# sch.net
KiCad netlist of a schematic drawn in EasyEDA
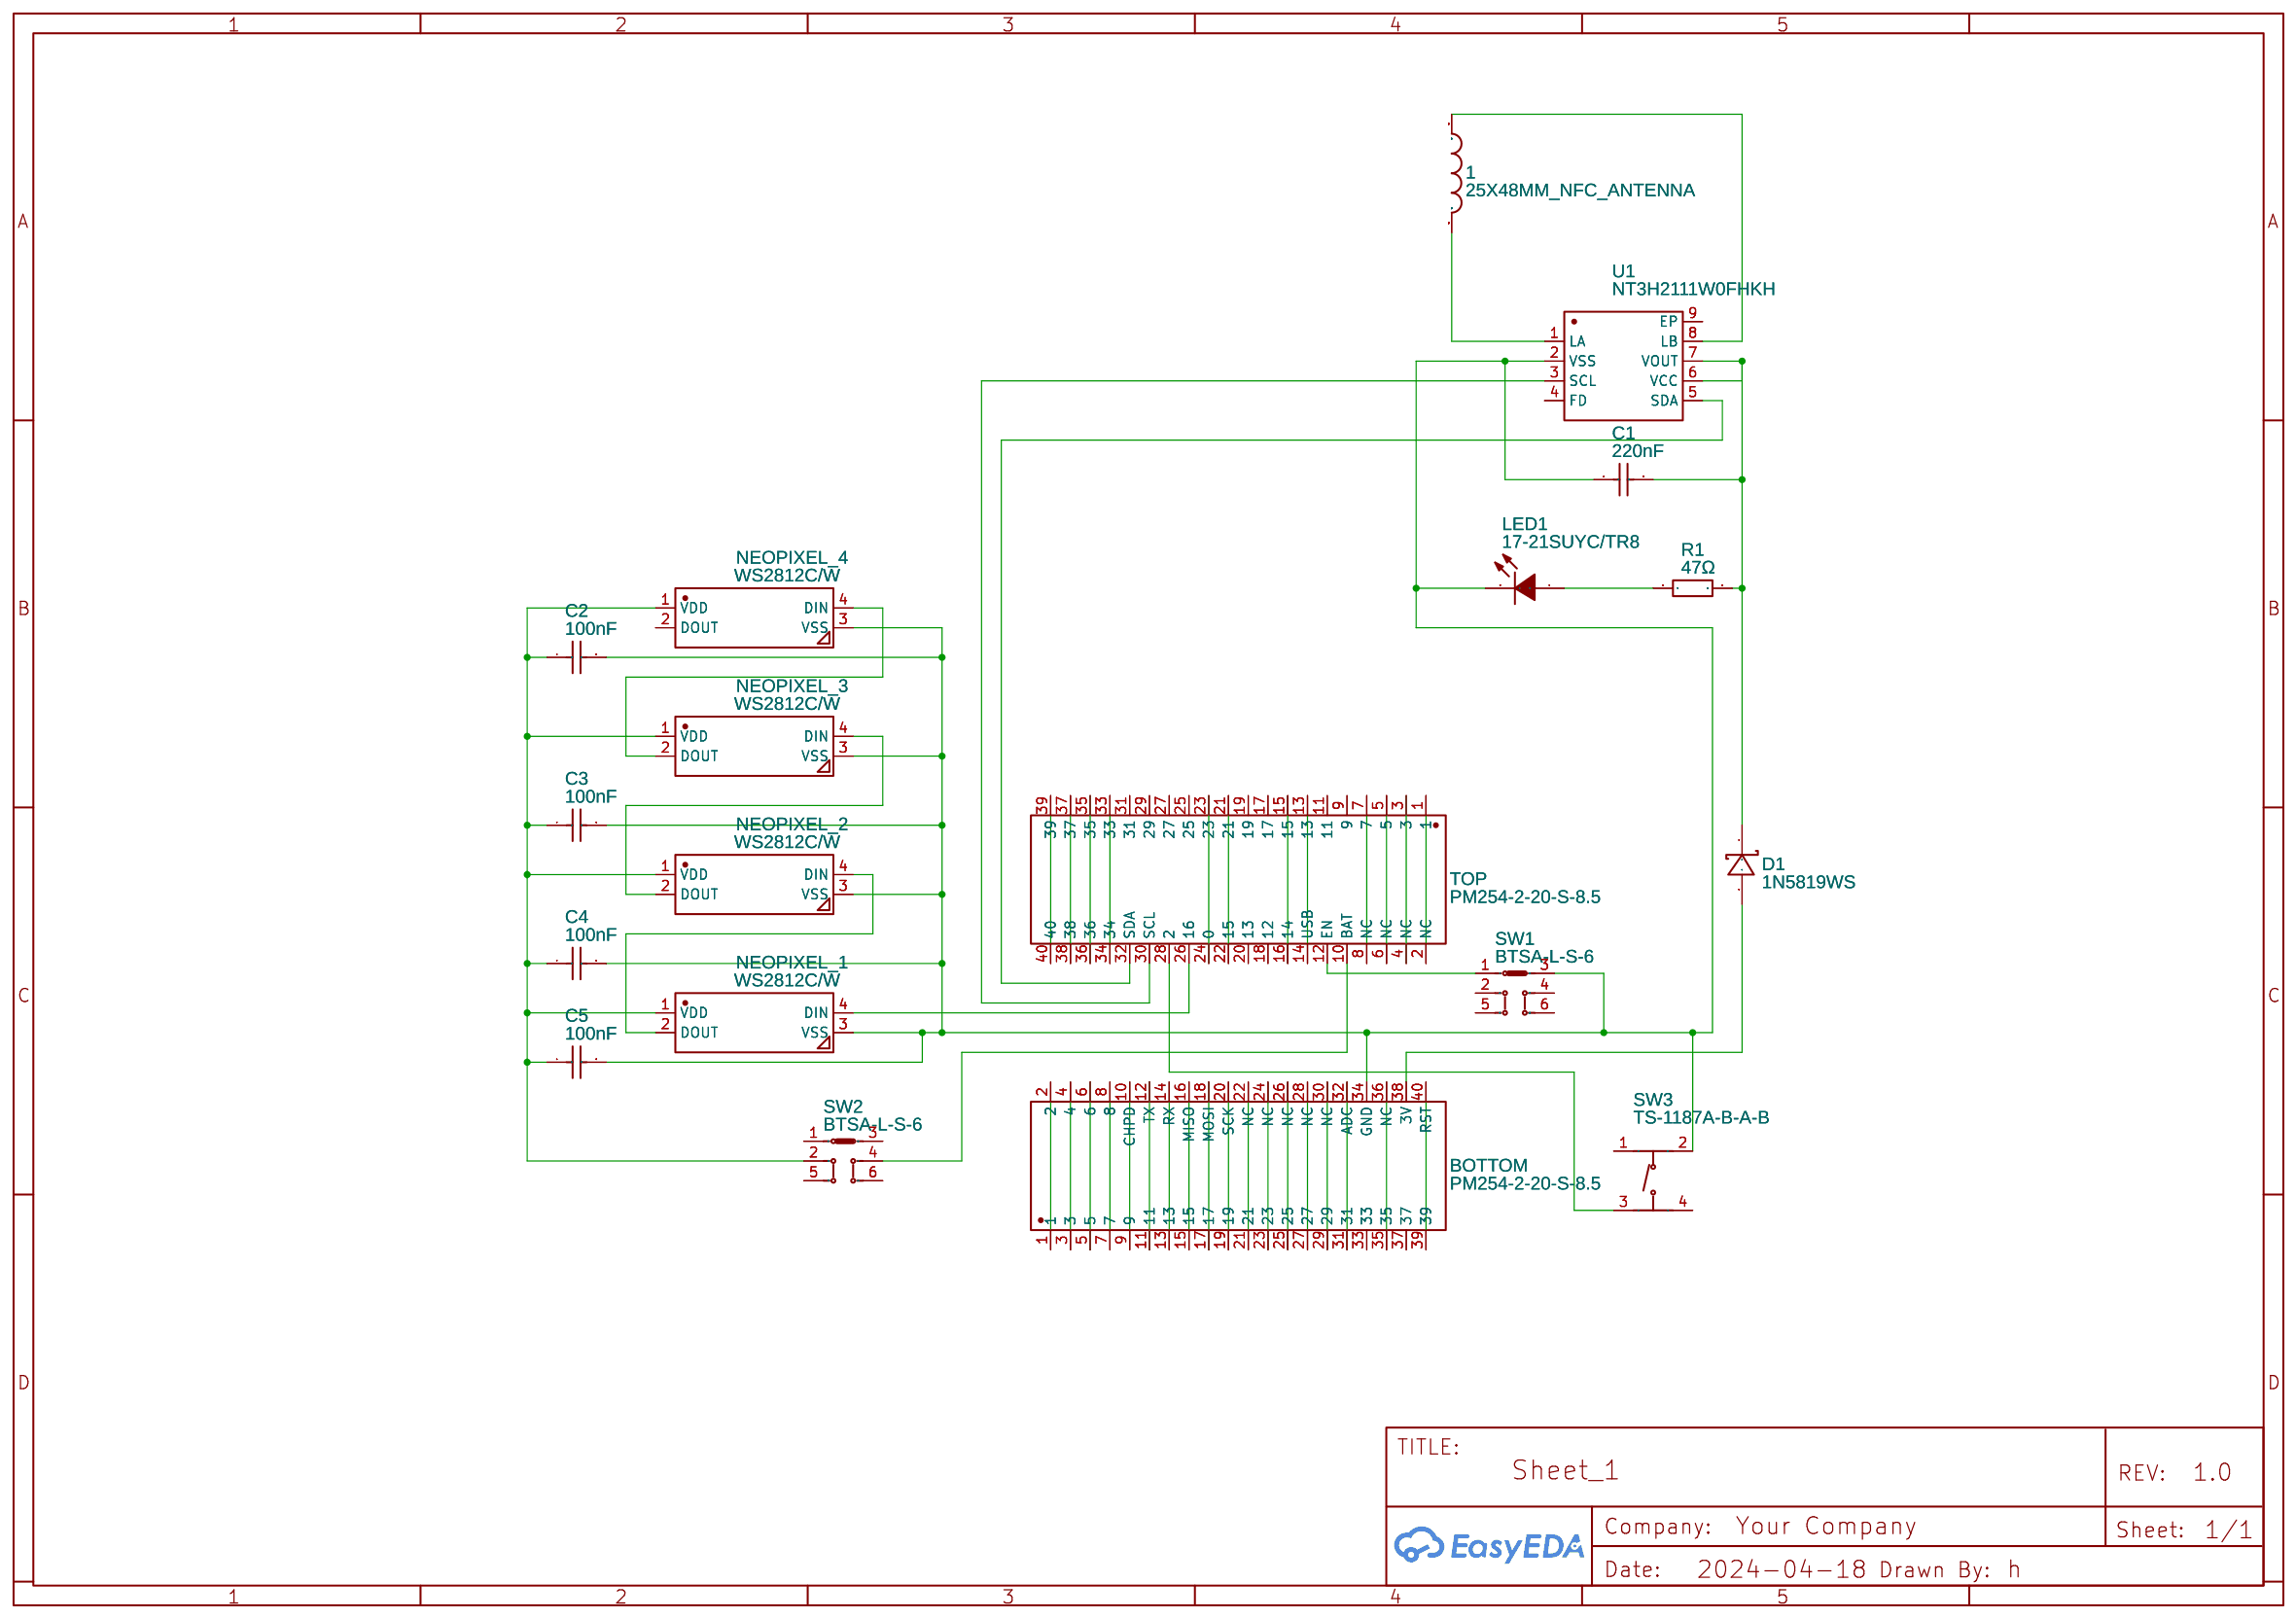
[diagram p0: schematic sheet]

(export (version "E")
  (design (tool "Eeschema 10.0.6"))
  (components
    (comp (ref "1") (value "25X48MM_NFC_ANTENNA") (libsource (lib "") (part "25X48MM_NFC_ANTENNA")))
    (comp (ref "BOTTOM")
      (value "PM254-2-20-S-8.5")
      (fields (field (name "Manufacturer") "HCTL(华灿天禄)"))
      (libsource (lib "") (part "PM254-2-20-S-8.5_1"))
    )
    (comp (ref "C1")
      (value "220nF")
      (fields
        (field (name "Manufacturer Part") "CL10B224KA8NNNC")
        (field (name "Manufacturer") "SAMSUNG(三星)")
      )
      (libsource (lib "") (part "CL10B224KA8NNNC"))
    )
    (comp (ref "C2")
      (value "100nF")
      (fields (field (name "Manufacturer Part") "CL05B104KO5NNNC") (field (name "Manufacturer") "SAMSUNG"))
      (libsource (lib "") (part "CL05B104KO5NNNC COPY"))
    )
    (comp (ref "C3")
      (value "100nF")
      (fields (field (name "Manufacturer Part") "CL05B104KO5NNNC") (field (name "Manufacturer") "SAMSUNG"))
      (libsource (lib "") (part "CL05B104KO5NNNC COPY"))
    )
    (comp (ref "C4")
      (value "100nF")
      (fields (field (name "Manufacturer Part") "CL05B104KO5NNNC") (field (name "Manufacturer") "SAMSUNG"))
      (libsource (lib "") (part "CL05B104KO5NNNC COPY"))
    )
    (comp (ref "C5")
      (value "100nF")
      (fields (field (name "Manufacturer Part") "CL05B104KO5NNNC") (field (name "Manufacturer") "SAMSUNG"))
      (libsource (lib "") (part "CL05B104KO5NNNC COPY"))
    )
    (comp (ref "D1")
      (value "1N5819WS")
      (fields (field (name "Manufacturer") "Hottech(合科泰)"))
      (libsource (lib "") (part "1N5819WS"))
    )
    (comp (ref "LED1")
      (value "17-21SUYC/TR8")
      (fields (field (name "Manufacturer Part") "KT-0805黄灯") (field (name "Manufacturer") "KENTO"))
      (libsource (lib "") (part "17-21SUYC/TR8"))
    )
    (comp (ref "NEOPIXEL_1")
      (value "WS2812C/W")
      (fields (field (name "Manufacturer") "worldsemi"))
      (libsource (lib "") (part "WS2812C/W"))
    )
    (comp (ref "NEOPIXEL_2")
      (value "WS2812C/W")
      (fields (field (name "Manufacturer") "worldsemi"))
      (libsource (lib "") (part "WS2812C/W"))
    )
    (comp (ref "NEOPIXEL_3")
      (value "WS2812C/W")
      (fields (field (name "Manufacturer") "worldsemi"))
      (libsource (lib "") (part "WS2812C/W"))
    )
    (comp (ref "NEOPIXEL_4")
      (value "WS2812C/W")
      (fields (field (name "Manufacturer") "worldsemi"))
      (libsource (lib "") (part "WS2812C/W"))
    )
    (comp (ref "R1")
      (value "47Ω")
      (fields
        (field (name "Manufacturer Part") "0603WAF470JT5E")
        (field (name "Manufacturer") "UNI-ROYAL(厚声)")
      )
      (libsource (lib "") (part "0603WAF470JT5E"))
    )
    (comp (ref "SW1")
      (value "BTSA-L-S-6")
      (fields (field (name "Manufacturer") "ROCPU Switches(台普)"))
      (libsource (lib "") (part "BTSA-L-S-6"))
    )
    (comp (ref "SW2")
      (value "BTSA-L-S-6")
      (fields (field (name "Manufacturer") "ROCPU Switches(台普)"))
      (libsource (lib "") (part "BTSA-L-S-6"))
    )
    (comp (ref "SW3")
      (value "TS-1187A-B-A-B")
      (fields (field (name "Manufacturer") "XKB Connectivity(中国星坤)"))
      (libsource (lib "") (part "TS-1187A-B-A-B"))
    )
    (comp (ref "TOP")
      (value "PM254-2-20-S-8.5")
      (fields (field (name "Manufacturer") "HCTL(华灿天禄)"))
      (libsource (lib "") (part "PM254-2-20-S-8.5"))
    )
    (comp (ref "U1")
      (value "NT3H2111W0FHKH")
      (fields (field (name "Manufacturer") "NXP(恩智浦)"))
      (libsource (lib "") (part "NT3H2111W0FHKH"))
    )
  )
  (nets
    (net (code "1") (name "Net-(BOTTOM-3V)") (class "Default")
      (node (ref "BOTTOM") (pin "38") (pinfunction "3V_38") (pintype "unspecified"))
      (node (ref "D1") (pin "2") (pinfunction "A_2") (pintype "unspecified"))
    )
    (net (code "2") (name "Net-(BOTTOM-ADC)") (class "Default")
      (node (ref "BOTTOM") (pin "31") (pinfunction "31_31") (pintype "unspecified"))
      (node (ref "BOTTOM") (pin "32") (pinfunction "ADC_32") (pintype "unspecified"))
    )
    (net (code "3") (name "Net-(BOTTOM-CHPD)") (class "Default")
      (node (ref "BOTTOM") (pin "10") (pinfunction "CHPD_10") (pintype "unspecified"))
      (node (ref "BOTTOM") (pin "9") (pinfunction "9_9") (pintype "unspecified"))
    )
    (net (code "4") (name "Net-(BOTTOM-GND)") (class "Default")
      (node (ref "BOTTOM") (pin "34") (pinfunction "GND_34") (pintype "unspecified"))
      (node (ref "C1") (pin "1") (pinfunction "1_1") (pintype "input"))
      (node (ref "C2") (pin "2") (pinfunction "2_2") (pintype "input"))
      (node (ref "C3") (pin "2") (pinfunction "2_2") (pintype "input"))
      (node (ref "C4") (pin "2") (pinfunction "2_2") (pintype "input"))
      (node (ref "C5") (pin "2") (pinfunction "2_2") (pintype "input"))
      (node (ref "LED1") (pin "2") (pinfunction "-_2") (pintype "unspecified"))
      (node (ref "NEOPIXEL_1") (pin "3") (pinfunction "VSS_3") (pintype "unspecified"))
      (node (ref "NEOPIXEL_2") (pin "3") (pinfunction "VSS_3") (pintype "unspecified"))
      (node (ref "NEOPIXEL_3") (pin "3") (pinfunction "VSS_3") (pintype "unspecified"))
      (node (ref "NEOPIXEL_4") (pin "3") (pinfunction "VSS_3") (pintype "unspecified"))
      (node (ref "SW1") (pin "3") (pinfunction "3_3") (pintype "unspecified"))
      (node (ref "SW3") (pin "2") (pinfunction "B_2") (pintype "unspecified"))
      (node (ref "U1") (pin "2") (pinfunction "VSS_2") (pintype "unspecified"))
    )
    (net (code "5") (name "Net-(BOTTOM-MISO)") (class "Default")
      (node (ref "BOTTOM") (pin "15") (pinfunction "15_15") (pintype "unspecified"))
      (node (ref "BOTTOM") (pin "16") (pinfunction "MISO_16") (pintype "unspecified"))
    )
    (net (code "6") (name "Net-(BOTTOM-MOSI)") (class "Default")
      (node (ref "BOTTOM") (pin "17") (pinfunction "17_17") (pintype "unspecified"))
      (node (ref "BOTTOM") (pin "18") (pinfunction "MOSI_18") (pintype "unspecified"))
    )
    (net (code "7") (name "Net-(BOTTOM-NC-Pad22)") (class "Default")
      (node (ref "BOTTOM") (pin "21") (pinfunction "21_21") (pintype "unspecified"))
      (node (ref "BOTTOM") (pin "22") (pinfunction "NC_22") (pintype "unspecified"))
    )
    (net (code "8") (name "Net-(BOTTOM-NC-Pad24)") (class "Default")
      (node (ref "BOTTOM") (pin "23") (pinfunction "23_23") (pintype "unspecified"))
      (node (ref "BOTTOM") (pin "24") (pinfunction "NC_24") (pintype "unspecified"))
    )
    (net (code "9") (name "Net-(BOTTOM-NC-Pad26)") (class "Default")
      (node (ref "BOTTOM") (pin "25") (pinfunction "25_25") (pintype "unspecified"))
      (node (ref "BOTTOM") (pin "26") (pinfunction "NC_26") (pintype "unspecified"))
    )
    (net (code "10") (name "Net-(BOTTOM-NC-Pad28)") (class "Default")
      (node (ref "BOTTOM") (pin "27") (pinfunction "27_27") (pintype "unspecified"))
      (node (ref "BOTTOM") (pin "28") (pinfunction "NC_28") (pintype "unspecified"))
    )
    (net (code "11") (name "Net-(BOTTOM-NC-Pad30)") (class "Default")
      (node (ref "BOTTOM") (pin "29") (pinfunction "29_29") (pintype "unspecified"))
      (node (ref "BOTTOM") (pin "30") (pinfunction "NC_30") (pintype "unspecified"))
    )
    (net (code "12") (name "Net-(BOTTOM-NC-Pad36)") (class "Default")
      (node (ref "BOTTOM") (pin "35") (pinfunction "35_35") (pintype "unspecified"))
      (node (ref "BOTTOM") (pin "36") (pinfunction "NC_36") (pintype "unspecified"))
    )
    (net (code "13") (name "Net-(BOTTOM-Pad1)") (class "Default")
      (node (ref "BOTTOM") (pin "1") (pinfunction "1_1") (pintype "unspecified"))
      (node (ref "BOTTOM") (pin "2") (pinfunction "2_2") (pintype "unspecified"))
    )
    (net (code "14") (name "Net-(BOTTOM-Pad3)") (class "Default")
      (node (ref "BOTTOM") (pin "3") (pinfunction "3_3") (pintype "unspecified"))
      (node (ref "BOTTOM") (pin "4") (pinfunction "4_4") (pintype "unspecified"))
    )
    (net (code "15") (name "Net-(BOTTOM-Pad5)") (class "Default")
      (node (ref "BOTTOM") (pin "5") (pinfunction "5_5") (pintype "unspecified"))
      (node (ref "BOTTOM") (pin "6") (pinfunction "6_6") (pintype "unspecified"))
    )
    (net (code "16") (name "Net-(BOTTOM-Pad7)") (class "Default")
      (node (ref "BOTTOM") (pin "7") (pinfunction "7_7") (pintype "unspecified"))
      (node (ref "BOTTOM") (pin "8") (pinfunction "8_8") (pintype "unspecified"))
    )
    (net (code "17") (name "Net-(BOTTOM-RST)") (class "Default")
      (node (ref "BOTTOM") (pin "39") (pinfunction "39_39") (pintype "unspecified"))
      (node (ref "BOTTOM") (pin "40") (pinfunction "RST_40") (pintype "unspecified"))
    )
    (net (code "18") (name "Net-(BOTTOM-RX)") (class "Default")
      (node (ref "BOTTOM") (pin "13") (pinfunction "13_13") (pintype "unspecified"))
      (node (ref "BOTTOM") (pin "14") (pinfunction "RX_14") (pintype "unspecified"))
    )
    (net (code "19") (name "Net-(BOTTOM-SCK)") (class "Default")
      (node (ref "BOTTOM") (pin "19") (pinfunction "19_19") (pintype "unspecified"))
      (node (ref "BOTTOM") (pin "20") (pinfunction "SCK_20") (pintype "unspecified"))
    )
    (net (code "20") (name "Net-(BOTTOM-TX)") (class "Default")
      (node (ref "BOTTOM") (pin "11") (pinfunction "11_11") (pintype "unspecified"))
      (node (ref "BOTTOM") (pin "12") (pinfunction "TX_12") (pintype "unspecified"))
    )
    (net (code "21") (name "Net-(D1-K)") (class "Default")
      (node (ref "C1") (pin "2") (pinfunction "2_2") (pintype "input"))
      (node (ref "D1") (pin "1") (pinfunction "K_1") (pintype "unspecified"))
      (node (ref "R1") (pin "2") (pinfunction "2_2") (pintype "input"))
      (node (ref "U1") (pin "6") (pinfunction "VCC_6") (pintype "unspecified"))
      (node (ref "U1") (pin "7") (pinfunction "VOUT_7") (pintype "unspecified"))
    )
    (net (code "22") (name "Net-(LED1-+)") (class "Default")
      (node (ref "LED1") (pin "1") (pinfunction "+_1") (pintype "unspecified"))
      (node (ref "R1") (pin "1") (pinfunction "1_1") (pintype "input"))
    )
    (net (code "23") (name "Net-(NEOPIXEL_1-DIN)") (class "Default")
      (node (ref "NEOPIXEL_1") (pin "4") (pinfunction "DIN_4") (pintype "unspecified"))
      (node (ref "TOP") (pin "26") (pinfunction "16_26") (pintype "unspecified"))
    )
    (net (code "24") (name "Net-(NEOPIXEL_1-DOUT)") (class "Default")
      (node (ref "NEOPIXEL_1") (pin "2") (pinfunction "DOUT_2") (pintype "unspecified"))
      (node (ref "NEOPIXEL_2") (pin "4") (pinfunction "DIN_4") (pintype "unspecified"))
    )
    (net (code "25") (name "Net-(NEOPIXEL_1-VDD)") (class "Default")
      (node (ref "C2") (pin "1") (pinfunction "1_1") (pintype "input"))
      (node (ref "C3") (pin "1") (pinfunction "1_1") (pintype "input"))
      (node (ref "C4") (pin "1") (pinfunction "1_1") (pintype "input"))
      (node (ref "C5") (pin "1") (pinfunction "1_1") (pintype "input"))
      (node (ref "NEOPIXEL_1") (pin "1") (pinfunction "VDD_1") (pintype "unspecified"))
      (node (ref "NEOPIXEL_2") (pin "1") (pinfunction "VDD_1") (pintype "unspecified"))
      (node (ref "NEOPIXEL_3") (pin "1") (pinfunction "VDD_1") (pintype "unspecified"))
      (node (ref "NEOPIXEL_4") (pin "1") (pinfunction "VDD_1") (pintype "unspecified"))
      (node (ref "SW2") (pin "2") (pinfunction "2_2") (pintype "unspecified"))
    )
    (net (code "26") (name "Net-(NEOPIXEL_2-DOUT)") (class "Default")
      (node (ref "NEOPIXEL_2") (pin "2") (pinfunction "DOUT_2") (pintype "unspecified"))
      (node (ref "NEOPIXEL_3") (pin "4") (pinfunction "DIN_4") (pintype "unspecified"))
    )
    (net (code "27") (name "Net-(NEOPIXEL_3-DOUT)") (class "Default")
      (node (ref "NEOPIXEL_3") (pin "2") (pinfunction "DOUT_2") (pintype "unspecified"))
      (node (ref "NEOPIXEL_4") (pin "4") (pinfunction "DIN_4") (pintype "unspecified"))
    )
    (net (code "28") (name "Net-(SW3-C)") (class "Default")
      (node (ref "SW3") (pin "3") (pinfunction "C_3") (pintype "unspecified"))
      (node (ref "TOP") (pin "28") (pinfunction "2_28") (pintype "unspecified"))
    )
    (net (code "29") (name "Net-(TOP-0)") (class "Default")
      (node (ref "TOP") (pin "23") (pinfunction "23_23") (pintype "unspecified"))
      (node (ref "TOP") (pin "24") (pinfunction "0_24") (pintype "unspecified"))
    )
    (net (code "30") (name "Net-(TOP-14)") (class "Default")
      (node (ref "TOP") (pin "15") (pinfunction "15_15") (pintype "unspecified"))
      (node (ref "TOP") (pin "16") (pinfunction "14_16") (pintype "unspecified"))
    )
    (net (code "31") (name "Net-(TOP-15-Pad22)") (class "Default")
      (node (ref "TOP") (pin "21") (pinfunction "21_21") (pintype "unspecified"))
      (node (ref "TOP") (pin "22") (pinfunction "15_22") (pintype "unspecified"))
    )
    (net (code "32") (name "Net-(TOP-BAT)") (class "Default")
      (node (ref "SW2") (pin "4") (pinfunction "4_4") (pintype "unspecified"))
      (node (ref "TOP") (pin "10") (pinfunction "BAT_10") (pintype "unspecified"))
    )
    (net (code "33") (name "Net-(TOP-EN)") (class "Default")
      (node (ref "SW1") (pin "1") (pinfunction "1_1") (pintype "unspecified"))
      (node (ref "TOP") (pin "12") (pinfunction "EN_12") (pintype "unspecified"))
    )
    (net (code "34") (name "Net-(TOP-NC-Pad2)") (class "Default")
      (node (ref "TOP") (pin "1") (pinfunction "1_1") (pintype "unspecified"))
      (node (ref "TOP") (pin "2") (pinfunction "NC_2") (pintype "unspecified"))
    )
    (net (code "35") (name "Net-(TOP-NC-Pad4)") (class "Default")
      (node (ref "TOP") (pin "3") (pinfunction "3_3") (pintype "unspecified"))
      (node (ref "TOP") (pin "4") (pinfunction "NC_4") (pintype "unspecified"))
    )
    (net (code "36") (name "Net-(TOP-NC-Pad6)") (class "Default")
      (node (ref "TOP") (pin "5") (pinfunction "5_5") (pintype "unspecified"))
      (node (ref "TOP") (pin "6") (pinfunction "NC_6") (pintype "unspecified"))
    )
    (net (code "37") (name "Net-(TOP-NC-Pad8)") (class "Default")
      (node (ref "TOP") (pin "7") (pinfunction "7_7") (pintype "unspecified"))
      (node (ref "TOP") (pin "8") (pinfunction "NC_8") (pintype "unspecified"))
    )
    (net (code "38") (name "Net-(TOP-Pad33)") (class "Default")
      (node (ref "TOP") (pin "33") (pinfunction "33_33") (pintype "unspecified"))
      (node (ref "TOP") (pin "34") (pinfunction "34_34") (pintype "unspecified"))
    )
    (net (code "39") (name "Net-(TOP-Pad35)") (class "Default")
      (node (ref "TOP") (pin "35") (pinfunction "35_35") (pintype "unspecified"))
      (node (ref "TOP") (pin "36") (pinfunction "36_36") (pintype "unspecified"))
    )
    (net (code "40") (name "Net-(TOP-Pad37)") (class "Default")
      (node (ref "TOP") (pin "37") (pinfunction "37_37") (pintype "unspecified"))
      (node (ref "TOP") (pin "38") (pinfunction "38_38") (pintype "unspecified"))
    )
    (net (code "41") (name "Net-(TOP-Pad39)") (class "Default")
      (node (ref "TOP") (pin "39") (pinfunction "39_39") (pintype "unspecified"))
      (node (ref "TOP") (pin "40") (pinfunction "40_40") (pintype "unspecified"))
    )
    (net (code "42") (name "Net-(TOP-SCL)") (class "Default")
      (node (ref "TOP") (pin "30") (pinfunction "SCL_30") (pintype "unspecified"))
      (node (ref "U1") (pin "3") (pinfunction "SCL_3") (pintype "unspecified"))
    )
    (net (code "43") (name "Net-(TOP-SDA)") (class "Default")
      (node (ref "TOP") (pin "32") (pinfunction "SDA_32") (pintype "unspecified"))
      (node (ref "U1") (pin "5") (pinfunction "SDA_5") (pintype "unspecified"))
    )
    (net (code "44") (name "Net-(TOP-USB)") (class "Default")
      (node (ref "TOP") (pin "13") (pinfunction "13_13") (pintype "unspecified"))
      (node (ref "TOP") (pin "14") (pinfunction "USB_14") (pintype "unspecified"))
    )
    (net (code "45") (name "Net-(U1-LA)") (class "Default")
      (node (ref "1") (pin "P$2") (pinfunction "P$2_P$2") (pintype "bidirectional"))
      (node (ref "U1") (pin "1") (pinfunction "LA_1") (pintype "unspecified"))
    )
    (net (code "46") (name "Net-(U1-LB)") (class "Default")
      (node (ref "1") (pin "P$1") (pinfunction "P$1_P$1") (pintype "bidirectional"))
      (node (ref "U1") (pin "8") (pinfunction "LB_8") (pintype "unspecified"))
    )
    (net (code "47") (name "unconnected-(BOTTOM-Pad33)") (class "Default")
      (node (ref "BOTTOM") (pin "33") (pinfunction "33_33") (pintype "unspecified"))
    )
    (net (code "48") (name "unconnected-(BOTTOM-Pad37)") (class "Default")
      (node (ref "BOTTOM") (pin "37") (pinfunction "37_37") (pintype "unspecified"))
    )
    (net (code "49") (name "unconnected-(NEOPIXEL_4-DOUT-Pad2)") (class "Default")
      (node (ref "NEOPIXEL_4") (pin "2") (pinfunction "DOUT_2") (pintype "unspecified"))
    )
    (net (code "50") (name "unconnected-(SW1-Pad2)") (class "Default")
      (node (ref "SW1") (pin "2") (pinfunction "2_2") (pintype "unspecified"))
    )
    (net (code "51") (name "unconnected-(SW1-Pad4)") (class "Default")
      (node (ref "SW1") (pin "4") (pinfunction "4_4") (pintype "unspecified"))
    )
    (net (code "52") (name "unconnected-(SW1-Pad5)") (class "Default")
      (node (ref "SW1") (pin "5") (pinfunction "5_5") (pintype "unspecified"))
    )
    (net (code "53") (name "unconnected-(SW1-Pad6)") (class "Default")
      (node (ref "SW1") (pin "6") (pinfunction "6_6") (pintype "unspecified"))
    )
    (net (code "54") (name "unconnected-(SW2-Pad1)") (class "Default")
      (node (ref "SW2") (pin "1") (pinfunction "1_1") (pintype "unspecified"))
    )
    (net (code "55") (name "unconnected-(SW2-Pad3)") (class "Default")
      (node (ref "SW2") (pin "3") (pinfunction "3_3") (pintype "unspecified"))
    )
    (net (code "56") (name "unconnected-(SW2-Pad5)") (class "Default")
      (node (ref "SW2") (pin "5") (pinfunction "5_5") (pintype "unspecified"))
    )
    (net (code "57") (name "unconnected-(SW2-Pad6)") (class "Default")
      (node (ref "SW2") (pin "6") (pinfunction "6_6") (pintype "unspecified"))
    )
    (net (code "58") (name "unconnected-(SW3-A-Pad1)") (class "Default")
      (node (ref "SW3") (pin "1") (pinfunction "A_1") (pintype "unspecified"))
    )
    (net (code "59") (name "unconnected-(SW3-D-Pad4)") (class "Default")
      (node (ref "SW3") (pin "4") (pinfunction "D_4") (pintype "unspecified"))
    )
    (net (code "60") (name "unconnected-(TOP-12-Pad18)") (class "Default")
      (node (ref "TOP") (pin "18") (pinfunction "12_18") (pintype "unspecified"))
    )
    (net (code "61") (name "unconnected-(TOP-13-Pad20)") (class "Default")
      (node (ref "TOP") (pin "20") (pinfunction "13_20") (pintype "unspecified"))
    )
    (net (code "62") (name "unconnected-(TOP-Pad9)") (class "Default")
      (node (ref "TOP") (pin "9") (pinfunction "9_9") (pintype "unspecified"))
    )
    (net (code "63") (name "unconnected-(TOP-Pad11)") (class "Default")
      (node (ref "TOP") (pin "11") (pinfunction "11_11") (pintype "unspecified"))
    )
    (net (code "64") (name "unconnected-(TOP-Pad17)") (class "Default")
      (node (ref "TOP") (pin "17") (pinfunction "17_17") (pintype "unspecified"))
    )
    (net (code "65") (name "unconnected-(TOP-Pad19)") (class "Default")
      (node (ref "TOP") (pin "19") (pinfunction "19_19") (pintype "unspecified"))
    )
    (net (code "66") (name "unconnected-(TOP-Pad25)") (class "Default")
      (node (ref "TOP") (pin "25") (pinfunction "25_25") (pintype "unspecified"))
    )
    (net (code "67") (name "unconnected-(TOP-Pad27)") (class "Default")
      (node (ref "TOP") (pin "27") (pinfunction "27_27") (pintype "unspecified"))
    )
    (net (code "68") (name "unconnected-(TOP-Pad29)") (class "Default")
      (node (ref "TOP") (pin "29") (pinfunction "29_29") (pintype "unspecified"))
    )
    (net (code "69") (name "unconnected-(TOP-Pad31)") (class "Default")
      (node (ref "TOP") (pin "31") (pinfunction "31_31") (pintype "unspecified"))
    )
    (net (code "70") (name "unconnected-(U1-EP-Pad9)") (class "Default")
      (node (ref "U1") (pin "9") (pinfunction "EP_9") (pintype "unspecified"))
    )
    (net (code "71") (name "unconnected-(U1-FD-Pad4)") (class "Default")
      (node (ref "U1") (pin "4") (pinfunction "FD_4") (pintype "unspecified"))
    )
  )
)
